# Counting_Box.net
KiCad netlist of a schematic drawn in EAGLE
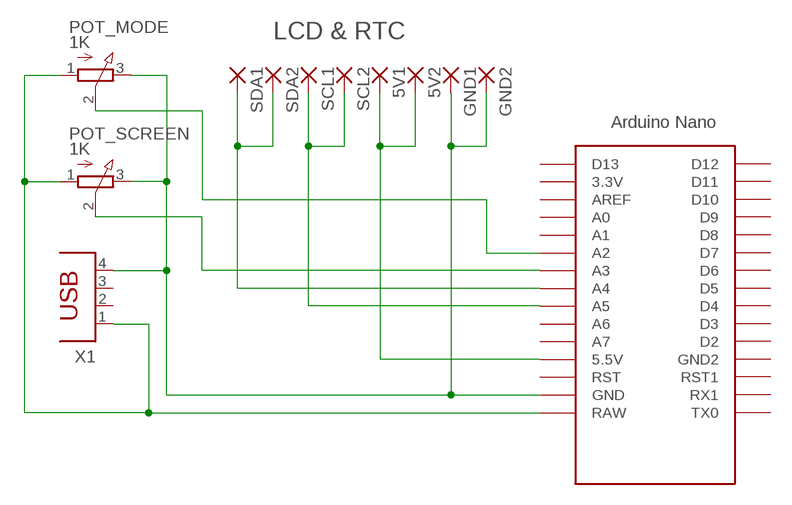
[diagram p0: schematic, sheet 1]

(export (version "E")
  (design (tool "Eeschema 10.0.6"))
  (components
    (comp (ref "5V1")
      (value "SMD2")
      (footprint "eagle-import:SMD1,27-2,54")
      (libsource (lib "eagle-import") (part "SMD2"))
    )
    (comp (ref "5V2")
      (value "SMD2")
      (footprint "eagle-import:SMD1,27-2,54")
      (libsource (lib "eagle-import") (part "SMD2"))
    )
    (comp (ref "GND1")
      (value "SMD2")
      (footprint "eagle-import:SMD1,27-2,54")
      (libsource (lib "eagle-import") (part "SMD2"))
    )
    (comp (ref "GND2")
      (value "SMD2")
      (footprint "eagle-import:SMD1,27-2,54")
      (libsource (lib "eagle-import") (part "SMD2"))
    )
    (comp (ref "POT_MODE")
      (value "1K")
      (footprint "eagle-import:3RP_1610N")
      (libsource (lib "eagle-import") (part "3RP/1610N"))
    )
    (comp (ref "POT_SCREEN")
      (value "1K")
      (footprint "eagle-import:3RP_1610N")
      (libsource (lib "eagle-import") (part "3RP/1610N"))
    )
    (comp (ref "SCL1")
      (value "SMD2")
      (footprint "eagle-import:SMD1,27-2,54")
      (libsource (lib "eagle-import") (part "SMD2"))
    )
    (comp (ref "SCL2")
      (value "SMD2")
      (footprint "eagle-import:SMD1,27-2,54")
      (libsource (lib "eagle-import") (part "SMD2"))
    )
    (comp (ref "SDA1")
      (value "SMD2")
      (footprint "eagle-import:SMD1,27-2,54")
      (libsource (lib "eagle-import") (part "SMD2"))
    )
    (comp (ref "SDA2")
      (value "SMD2")
      (footprint "eagle-import:SMD1,27-2,54")
      (libsource (lib "eagle-import") (part "SMD2"))
    )
    (comp (ref "U$1")
      (value "NANO")
      (footprint "eagle-import:NANO")
      (libsource (lib "eagle-import") (part "NANO"))
    )
    (comp (ref "X1")
      (value "PN87520")
      (footprint "eagle-import:PN87520")
      (libsource (lib "eagle-import") (part "PN87520"))
    )
  )
  (nets
    (net (code "1") (name "Net-(5V1-P)") (class "Default")
      (node (ref "5V1") (pin "1") (pinfunction "P_1") (pintype "passive"))
      (node (ref "5V2") (pin "1") (pinfunction "P_1") (pintype "passive"))
      (node (ref "U$1") (pin "5V") (pinfunction "5.5V_5V") (pintype "bidirectional"))
    )
    (net (code "2") (name "Net-(GND1-P)") (class "Default")
      (node (ref "GND1") (pin "1") (pinfunction "P_1") (pintype "passive"))
      (node (ref "GND2") (pin "1") (pinfunction "P_1") (pintype "passive"))
      (node (ref "POT_MODE") (pin "3") (pinfunction "E_3") (pintype "passive"))
      (node (ref "POT_SCREEN") (pin "3") (pinfunction "E_3") (pintype "passive"))
      (node (ref "U$1") (pin "GND") (pinfunction "GND_GND") (pintype "bidirectional"))
      (node (ref "X1") (pin "4") (pinfunction "4_4") (pintype "passive"))
    )
    (net (code "3") (name "Net-(POT_MODE-A)") (class "Default")
      (node (ref "POT_MODE") (pin "1") (pinfunction "A_1") (pintype "passive"))
      (node (ref "POT_SCREEN") (pin "1") (pinfunction "A_1") (pintype "passive"))
      (node (ref "U$1") (pin "RAW") (pinfunction "RAW_RAW") (pintype "bidirectional"))
      (node (ref "X1") (pin "1") (pinfunction "1_1") (pintype "passive"))
    )
    (net (code "4") (name "Net-(POT_MODE-S)") (class "Default")
      (node (ref "POT_MODE") (pin "2") (pinfunction "S_2") (pintype "passive"))
      (node (ref "U$1") (pin "A2") (pinfunction "A2_A2") (pintype "bidirectional"))
    )
    (net (code "5") (name "Net-(POT_SCREEN-S)") (class "Default")
      (node (ref "POT_SCREEN") (pin "2") (pinfunction "S_2") (pintype "passive"))
      (node (ref "U$1") (pin "A3") (pinfunction "A3_A3") (pintype "bidirectional"))
    )
    (net (code "6") (name "Net-(SCL1-P)") (class "Default")
      (node (ref "SCL1") (pin "1") (pinfunction "P_1") (pintype "passive"))
      (node (ref "SCL2") (pin "1") (pinfunction "P_1") (pintype "passive"))
      (node (ref "U$1") (pin "A5") (pinfunction "A5_A5") (pintype "bidirectional"))
    )
    (net (code "7") (name "Net-(SDA1-P)") (class "Default")
      (node (ref "SDA1") (pin "1") (pinfunction "P_1") (pintype "passive"))
      (node (ref "SDA2") (pin "1") (pinfunction "P_1") (pintype "passive"))
      (node (ref "U$1") (pin "A4") (pinfunction "A4_A4") (pintype "bidirectional"))
    )
    (net (code "8") (name "unconnected-(U$1-GND2-PadGND1)") (class "Default")
      (node (ref "U$1") (pin "GND1") (pinfunction "GND2_GND1") (pintype "bidirectional"))
    )
    (net (code "9") (name "unconnected-(U$1-Pad3.3V)") (class "Default")
      (node (ref "U$1") (pin "3.3V") (pinfunction "3.3V_3.3V") (pintype "bidirectional"))
    )
    (net (code "10") (name "unconnected-(U$1-PadA0)") (class "Default")
      (node (ref "U$1") (pin "A0") (pinfunction "A0_A0") (pintype "bidirectional"))
    )
    (net (code "11") (name "unconnected-(U$1-PadA1)") (class "Default")
      (node (ref "U$1") (pin "A1") (pinfunction "A1_A1") (pintype "bidirectional"))
    )
    (net (code "12") (name "unconnected-(U$1-PadA6)") (class "Default")
      (node (ref "U$1") (pin "A6") (pinfunction "A6_A6") (pintype "bidirectional"))
    )
    (net (code "13") (name "unconnected-(U$1-PadA7)") (class "Default")
      (node (ref "U$1") (pin "A7") (pinfunction "A7_A7") (pintype "bidirectional"))
    )
    (net (code "14") (name "unconnected-(U$1-PadAREF)") (class "Default")
      (node (ref "U$1") (pin "AREF") (pinfunction "AREF_AREF") (pintype "bidirectional"))
    )
    (net (code "15") (name "unconnected-(U$1-PadD2)") (class "Default")
      (node (ref "U$1") (pin "D2") (pinfunction "D2_D2") (pintype "bidirectional"))
    )
    (net (code "16") (name "unconnected-(U$1-PadD3)") (class "Default")
      (node (ref "U$1") (pin "D3") (pinfunction "D3_D3") (pintype "bidirectional"))
    )
    (net (code "17") (name "unconnected-(U$1-PadD4)") (class "Default")
      (node (ref "U$1") (pin "D4") (pinfunction "D4_D4") (pintype "bidirectional"))
    )
    (net (code "18") (name "unconnected-(U$1-PadD5)") (class "Default")
      (node (ref "U$1") (pin "D5") (pinfunction "D5_D5") (pintype "bidirectional"))
    )
    (net (code "19") (name "unconnected-(U$1-PadD6)") (class "Default")
      (node (ref "U$1") (pin "D6") (pinfunction "D6_D6") (pintype "bidirectional"))
    )
    (net (code "20") (name "unconnected-(U$1-PadD7)") (class "Default")
      (node (ref "U$1") (pin "D7") (pinfunction "D7_D7") (pintype "bidirectional"))
    )
    (net (code "21") (name "unconnected-(U$1-PadD8)") (class "Default")
      (node (ref "U$1") (pin "D8") (pinfunction "D8_D8") (pintype "bidirectional"))
    )
    (net (code "22") (name "unconnected-(U$1-PadD9)") (class "Default")
      (node (ref "U$1") (pin "D9") (pinfunction "D9_D9") (pintype "bidirectional"))
    )
    (net (code "23") (name "unconnected-(U$1-PadD10)") (class "Default")
      (node (ref "U$1") (pin "D10") (pinfunction "D10_D10") (pintype "bidirectional"))
    )
    (net (code "24") (name "unconnected-(U$1-PadD11)") (class "Default")
      (node (ref "U$1") (pin "D11") (pinfunction "D11_D11") (pintype "bidirectional"))
    )
    (net (code "25") (name "unconnected-(U$1-PadD12)") (class "Default")
      (node (ref "U$1") (pin "D12") (pinfunction "D12_D12") (pintype "bidirectional"))
    )
    (net (code "26") (name "unconnected-(U$1-PadD13)") (class "Default")
      (node (ref "U$1") (pin "D13") (pinfunction "D13_D13") (pintype "bidirectional"))
    )
    (net (code "27") (name "unconnected-(U$1-PadICSP1)") (class "Default")
      (node (ref "U$1") (pin "ICSP1") (pinfunction "ICSP1_ICSP1") (pintype "bidirectional"))
    )
    (net (code "28") (name "unconnected-(U$1-PadICSP2)") (class "Default")
      (node (ref "U$1") (pin "ICSP2") (pinfunction "ICSP2_ICSP2") (pintype "bidirectional"))
    )
    (net (code "29") (name "unconnected-(U$1-PadICSP3)") (class "Default")
      (node (ref "U$1") (pin "ICSP3") (pinfunction "ICSP3_ICSP3") (pintype "bidirectional"))
    )
    (net (code "30") (name "unconnected-(U$1-PadICSP4)") (class "Default")
      (node (ref "U$1") (pin "ICSP4") (pinfunction "ICSP4_ICSP4") (pintype "bidirectional"))
    )
    (net (code "31") (name "unconnected-(U$1-PadICSP5)") (class "Default")
      (node (ref "U$1") (pin "ICSP5") (pinfunction "ICSP5_ICSP5") (pintype "bidirectional"))
    )
    (net (code "32") (name "unconnected-(U$1-PadICSP6)") (class "Default")
      (node (ref "U$1") (pin "ICSP6") (pinfunction "ICSP6_ICSP6") (pintype "bidirectional"))
    )
    (net (code "33") (name "unconnected-(U$1-PadRST)") (class "Default")
      (node (ref "U$1") (pin "RST") (pinfunction "RST_RST") (pintype "bidirectional"))
    )
    (net (code "34") (name "unconnected-(U$1-PadRST1)") (class "Default")
      (node (ref "U$1") (pin "RST1") (pinfunction "RST1_RST1") (pintype "bidirectional"))
    )
    (net (code "35") (name "unconnected-(U$1-PadRX1)") (class "Default")
      (node (ref "U$1") (pin "RX1") (pinfunction "RX1_RX1") (pintype "bidirectional"))
    )
    (net (code "36") (name "unconnected-(U$1-PadTX0)") (class "Default")
      (node (ref "U$1") (pin "TX0") (pinfunction "TX0_TX0") (pintype "bidirectional"))
    )
    (net (code "37") (name "unconnected-(X1-Pad2)") (class "Default")
      (node (ref "X1") (pin "2") (pinfunction "2_2") (pintype "passive"))
    )
    (net (code "38") (name "unconnected-(X1-Pad3)") (class "Default")
      (node (ref "X1") (pin "3") (pinfunction "3_3") (pintype "passive"))
    )
  )
)
